# Candunio.net
KiCad netlist of a schematic drawn in Altium Designer
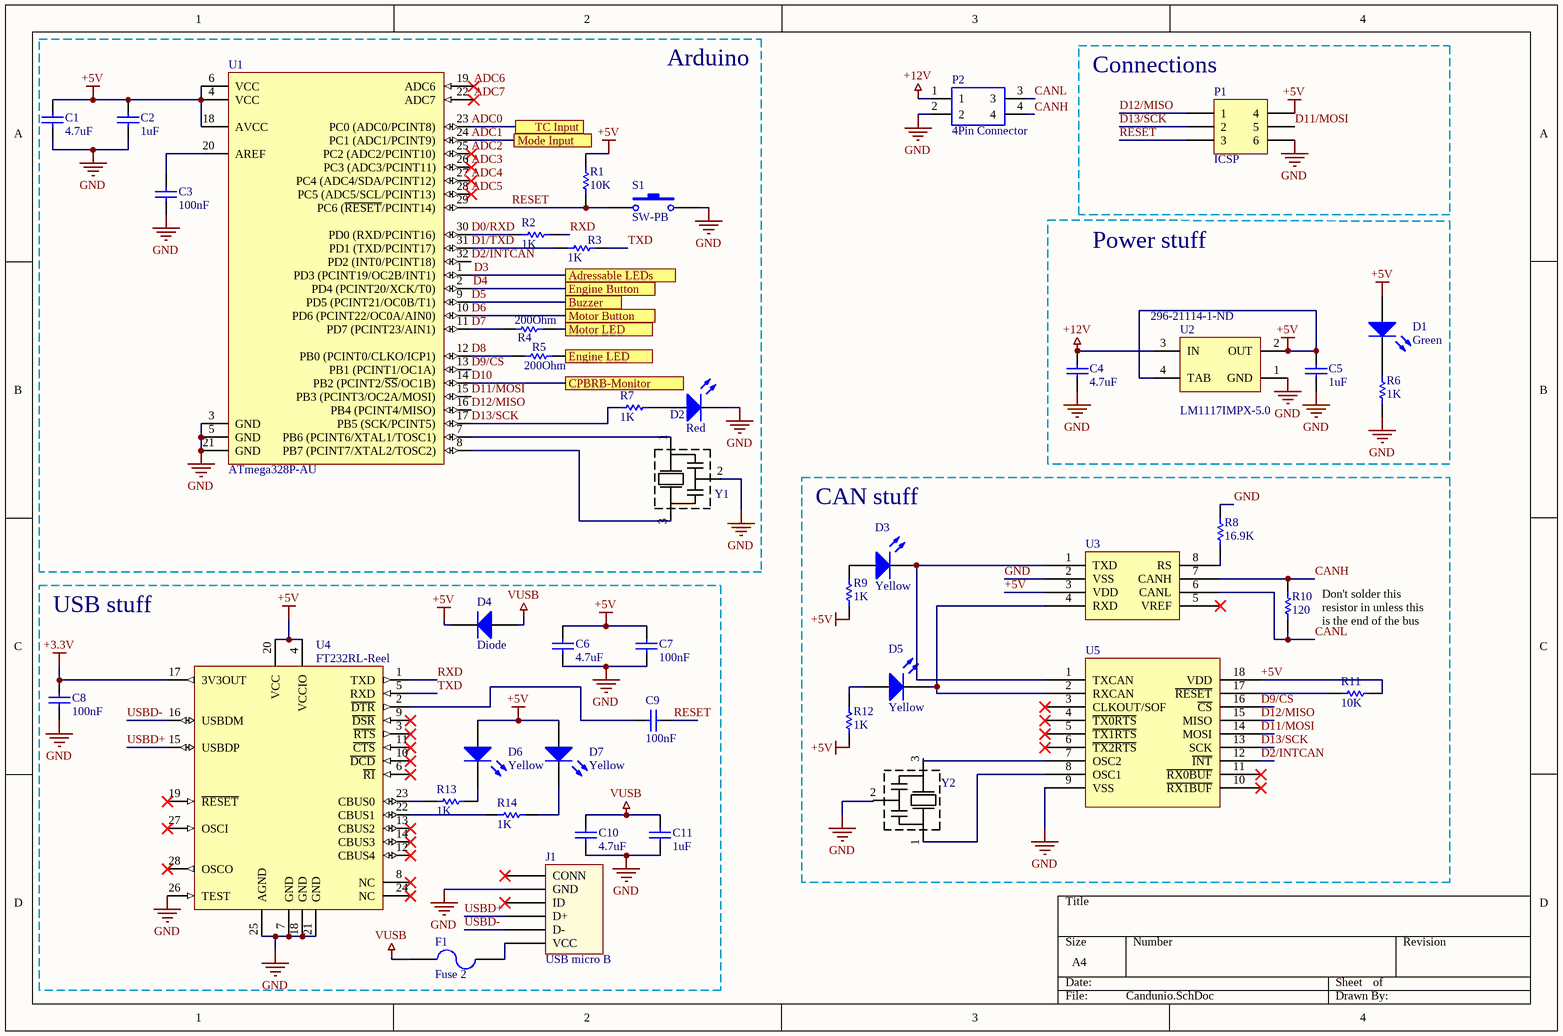
[diagram p0: Candunio.SchDoc]

(export (version "E")
  (design (tool "Eeschema 10.0.6"))
  (components
    (comp (ref "C1")
      (value "4.7uF")
      (footprint "CAPC3216X170N")
      (description "Capacitor (Semiconductor SIM Model)")
      (fields
        (field (name "MANUFACTURER") "Murata")
        (field (name "MANUFACTURER PART NUMBER") "GRM31MR71H105KA88L")
        (field (name "PUBLISHER") "Altium Limited")
      )
      (libsource (lib "Candunio v2018_7_27") (part "Cap Semi"))
    )
    (comp (ref "C2")
      (value "1uF")
      (footprint "CAPC3216X170N")
      (description "Capacitor (Semiconductor SIM Model)")
      (fields
        (field (name "MANUFACTURER") "Murata")
        (field (name "MANUFACTURER PART NUMBER") "GRM31MR71H105KA88L")
        (field (name "PUBLISHER") "Altium Limited")
      )
      (libsource (lib "Candunio v2018_7_27") (part "Cap Semi"))
    )
    (comp (ref "C3")
      (value "100nF")
      (footprint "CAPC3216X170N")
      (description "Capacitor (Semiconductor SIM Model)")
      (fields
        (field (name "MANUFACTURER") "Murata")
        (field (name "MANUFACTURER PART NUMBER") "GRM31MR71H105KA88L")
        (field (name "PUBLISHER") "Altium Limited")
      )
      (libsource (lib "Candunio v2018_7_27") (part "Cap Semi"))
    )
    (comp (ref "C4")
      (value "4.7uF")
      (footprint "CAPC3216X170N")
      (description "Capacitor (Semiconductor SIM Model)")
      (fields
        (field (name "MANUFACTURER") "Murata")
        (field (name "MANUFACTURER PART NUMBER") "GRM31MR71H105KA88L")
        (field (name "PUBLISHER") "Altium Limited")
      )
      (libsource (lib "Candunio v2018_7_27") (part "Cap Semi"))
    )
    (comp (ref "C5")
      (value "1uF")
      (footprint "CAPC3216X170N")
      (description "Capacitor (Semiconductor SIM Model)")
      (fields
        (field (name "MANUFACTURER") "Murata")
        (field (name "MANUFACTURER PART NUMBER") "GRM31MR71H105KA88L")
        (field (name "PUBLISHER") "Altium Limited")
      )
      (libsource (lib "Candunio v2018_7_27") (part "Cap Semi"))
    )
    (comp (ref "C6")
      (value "4.7uF")
      (footprint "CAPC3216X170N")
      (description "Capacitor (Semiconductor SIM Model)")
      (fields
        (field (name "MANUFACTURER") "Murata")
        (field (name "MANUFACTURER PART NUMBER") "GRM31MR71H105KA88L")
        (field (name "PUBLISHER") "Altium Limited")
      )
      (libsource (lib "Candunio v2018_7_27") (part "Cap Semi"))
    )
    (comp (ref "C7")
      (value "100nF")
      (footprint "CAPC3216X170N")
      (description "Capacitor (Semiconductor SIM Model)")
      (fields
        (field (name "MANUFACTURER") "Murata")
        (field (name "MANUFACTURER PART NUMBER") "GRM31MR71H105KA88L")
        (field (name "PUBLISHER") "Altium Limited")
      )
      (libsource (lib "Candunio v2018_7_27") (part "Cap Semi"))
    )
    (comp (ref "C8")
      (value "100nF")
      (footprint "CAPC3216X170N")
      (description "Capacitor (Semiconductor SIM Model)")
      (fields
        (field (name "MANUFACTURER") "Murata")
        (field (name "MANUFACTURER PART NUMBER") "GRM31MR71H105KA88L")
        (field (name "PUBLISHER") "Altium Limited")
      )
      (libsource (lib "Candunio v2018_7_27") (part "Cap Semi"))
    )
    (comp (ref "C9")
      (value "100nF")
      (footprint "CAPC3216X170N")
      (description "Capacitor (Semiconductor SIM Model)")
      (fields
        (field (name "MANUFACTURER") "Murata")
        (field (name "MANUFACTURER PART NUMBER") "GRM31MR71H105KA88L")
        (field (name "PUBLISHER") "Altium Limited")
      )
      (libsource (lib "Candunio v2018_7_27") (part "Cap Semi"))
    )
    (comp (ref "C10")
      (value "4.7uF")
      (footprint "CAPC3216X170N")
      (description "Capacitor (Semiconductor SIM Model)")
      (fields
        (field (name "MANUFACTURER") "Murata")
        (field (name "MANUFACTURER PART NUMBER") "GRM31MR71H105KA88L")
        (field (name "PUBLISHER") "Altium Limited")
      )
      (libsource (lib "Candunio v2018_7_27") (part "Cap Semi"))
    )
    (comp (ref "C11")
      (value "1uF")
      (footprint "CAPC3216X170N")
      (description "Capacitor (Semiconductor SIM Model)")
      (fields
        (field (name "MANUFACTURER") "Murata")
        (field (name "MANUFACTURER PART NUMBER") "GRM31MR71H105KA88L")
        (field (name "PUBLISHER") "Altium Limited")
      )
      (libsource (lib "Candunio v2018_7_27") (part "Cap Semi"))
    )
    (comp (ref "D1")
      (value "Green")
      (footprint "LEDC3216X120NGRN")
      (description "Typical RED, GREEN, YELLOW, AMBER GaAs LED")
      (fields
        (field (name "MANUFACTURER") "Broadcom Avago")
        (field (name "MANUFACTURER PART NUMBER") "HSMG-C150")
        (field (name "PUBLISHER") "Altium Limited")
      )
      (libsource (lib "Miscellaneous Devices") (part "LED2"))
    )
    (comp (ref "D2")
      (value "Red")
      (footprint "LEDC3216X120NRED")
      (description "Typical RED, GREEN, YELLOW, AMBER GaAs LED")
      (fields
        (field (name "MANUFACTURER") "Broadcom Avago")
        (field (name "MANUFACTURER PART NUMBER") "HSMY-C150")
        (field (name "PUBLISHER") "Altium Limited")
      )
      (libsource (lib "Miscellaneous Devices") (part "LED2"))
    )
    (comp (ref "D3")
      (value "Yellow")
      (footprint "LEDC3216X120NYEL")
      (description "Typical RED, GREEN, YELLOW, AMBER GaAs LED")
      (fields
        (field (name "MANUFACTURER") "Broadcom Avago")
        (field (name "MANUFACTURER PART NUMBER") "HSMY-C150")
        (field (name "PUBLISHER") "Altium Limited")
      )
      (libsource (lib "Miscellaneous Devices") (part "LED2"))
    )
    (comp (ref "D4")
      (value "Diode")
      (footprint "DO-220AA")
      (description "Default Diode")
      (fields (field (name "PUBLISHER") "Altium Limited"))
      (libsource (lib "Candunio") (part "Diode"))
    )
    (comp (ref "D5")
      (value "Yellow")
      (footprint "LEDC3216X120NYEL")
      (description "Typical RED, GREEN, YELLOW, AMBER GaAs LED")
      (fields
        (field (name "MANUFACTURER") "Broadcom Avago")
        (field (name "MANUFACTURER PART NUMBER") "HSMY-C150")
        (field (name "PUBLISHER") "Altium Limited")
      )
      (libsource (lib "Miscellaneous Devices") (part "LED2"))
    )
    (comp (ref "D6")
      (value "Yellow")
      (footprint "LEDC3216X120NYEL")
      (description "Typical RED, GREEN, YELLOW, AMBER GaAs LED")
      (fields
        (field (name "MANUFACTURER") "Broadcom Avago")
        (field (name "MANUFACTURER PART NUMBER") "HSMY-C150")
        (field (name "PUBLISHER") "Altium Limited")
      )
      (libsource (lib "Miscellaneous Devices") (part "LED2"))
    )
    (comp (ref "D7")
      (value "Yellow")
      (footprint "LEDC3216X120NYEL")
      (description "Typical RED, GREEN, YELLOW, AMBER GaAs LED")
      (fields
        (field (name "MANUFACTURER") "Broadcom Avago")
        (field (name "MANUFACTURER PART NUMBER") "HSMY-C150")
        (field (name "PUBLISHER") "Altium Limited")
      )
      (libsource (lib "Miscellaneous Devices") (part "LED2"))
    )
    (comp (ref "F1")
      (value "Fuse 2")
      (footprint "FUSC4632X85N")
      (description "Fuse")
      (fields
        (field (name "PART NUMBER") "MF-MSMF050-2")
        (field (name "MANUFACTURER") "Bourns")
        (field (name "PUBLISHER") "Altium Limited")
      )
      (libsource (lib "PowerDistLib") (part "Fuse 2"))
    )
    (comp (ref "J1")
      (value "USB micro B")
      (footprint "1050170001")
      (description "CONN SM TH USB MICRO MODIFIED FOR DRILL")
      (fields (field (name "PART NUMBER") "WM1399CT-ND"))
      (libsource (lib "electronpowered") (part "1050170001"))
    )
    (comp (ref "P1")
      (value "ICSP")
      (footprint "Pin Header 2x3 TH Pitch 2.54mm")
      (description "Header, 3-Pin, Dual row")
      (fields (field (name "PUBLISHER") "Altium Limited"))
      (libsource (lib "Miscellaneous Connectors") (part "Header 3X2A"))
    )
    (comp (ref "P2")
      (value "4Pin Connector")
      (footprint "4Pin connector Molex")
      (description "Connector Header Through Hole 4 position 0.118\" (3.00mm) \r\n0430450413")
      (fields (field (name "MANUFACTURER_PART_NUMBER") "0430450413"))
      (libsource (lib "Connectors") (part "4Pin Connector"))
    )
    (comp (ref "R1")
      (value "10K")
      (footprint "RESC3216X60N")
      (description "Resistor")
      (fields
        (field (name "MANUFACTURER") "Stackpole Electronics")
        (field (name "MANUFACTURER PART NUMBER") "RNCP1206FTD1K00")
      )
      (libsource (lib "Miscellaneous Devices") (part "Res1"))
    )
    (comp (ref "R2")
      (value "1K")
      (footprint "RESC3216X60N")
      (description "Resistor")
      (fields
        (field (name "MANUFACTURER") "Stackpole Electronics")
        (field (name "MANUFACTURER PART NUMBER") "RNCP1206FTD1K00")
      )
      (libsource (lib "Miscellaneous Devices") (part "Res1"))
    )
    (comp (ref "R3")
      (value "1K")
      (footprint "RESC3216X60N")
      (description "Resistor")
      (fields
        (field (name "MANUFACTURER") "Stackpole Electronics")
        (field (name "MANUFACTURER PART NUMBER") "RNCP1206FTD1K00")
      )
      (libsource (lib "Miscellaneous Devices") (part "Res1"))
    )
    (comp (ref "R4")
      (value "200Ohm")
      (footprint "RESC3216X60N")
      (description "Resistor")
      (fields
        (field (name "MANUFACTURER") "Stackpole Electronics")
        (field (name "MANUFACTURER PART NUMBER") "RNCP1206FTD200R")
      )
      (libsource (lib "Miscellaneous Devices") (part "Res1"))
    )
    (comp (ref "R5")
      (value "200Ohm")
      (footprint "RESC3216X60N")
      (description "Resistor")
      (fields
        (field (name "MANUFACTURER") "Stackpole Electronics")
        (field (name "MANUFACTURER PART NUMBER") "RNCP1206FTD200R")
      )
      (libsource (lib "Miscellaneous Devices") (part "Res1"))
    )
    (comp (ref "R6")
      (value "1K")
      (footprint "RESC3216X60N")
      (description "Resistor")
      (fields
        (field (name "MANUFACTURER") "Stackpole Electronics")
        (field (name "MANUFACTURER PART NUMBER") "RNCP1206FTD1K00")
      )
      (libsource (lib "Miscellaneous Devices") (part "Res1"))
    )
    (comp (ref "R7")
      (value "1K")
      (footprint "RESC3216X60N")
      (description "Resistor")
      (fields
        (field (name "MANUFACTURER") "Stackpole Electronics")
        (field (name "MANUFACTURER PART NUMBER") "RNCP1206FTD1K00")
      )
      (libsource (lib "Miscellaneous Devices") (part "Res1"))
    )
    (comp (ref "R8")
      (value "16.9K")
      (footprint "RESC3216X60N")
      (description "Resistor")
      (fields
        (field (name "MANUFACTURER") "TE Connectivity Holsworthy")
        (field (name "MANUFACTURER PART NUMBER") "CRGH1206F16K9")
      )
      (libsource (lib "Miscellaneous Devices") (part "Res1"))
    )
    (comp (ref "R9")
      (value "1K")
      (footprint "RESC3216X60N")
      (description "Resistor")
      (fields
        (field (name "MANUFACTURER") "Stackpole Electronics")
        (field (name "MANUFACTURER PART NUMBER") "RNCP1206FTD1K00")
      )
      (libsource (lib "Miscellaneous Devices") (part "Res1"))
    )
    (comp (ref "R10")
      (value "120")
      (footprint "RESC3216X60N")
      (description "Resistor")
      (fields
        (field (name "MANUFACTURER") "Vishay")
        (field (name "MANUFACTURER PART NUMBER") "CRCW1206120RFKEAHP")
      )
      (libsource (lib "Miscellaneous Devices") (part "Res1"))
    )
    (comp (ref "R11")
      (value "10K")
      (footprint "RESC3216X60N")
      (description "Resistor")
      (fields
        (field (name "MANUFACTURER") "Stackpole Electronics")
        (field (name "MANUFACTURER PART NUMBER") "RNCP1206FTD10K0")
      )
      (libsource (lib "Miscellaneous Devices") (part "Res1"))
    )
    (comp (ref "R12")
      (value "1K")
      (footprint "RESC3216X60N")
      (description "Resistor")
      (fields
        (field (name "MANUFACTURER") "Stackpole Electronics")
        (field (name "MANUFACTURER PART NUMBER") "RNCP1206FTD1K00")
      )
      (libsource (lib "Miscellaneous Devices") (part "Res1"))
    )
    (comp (ref "R13")
      (value "1K")
      (footprint "RESC3216X60N")
      (description "Resistor")
      (fields
        (field (name "MANUFACTURER") "Stackpole Electronics")
        (field (name "MANUFACTURER PART NUMBER") "RNCP1206FTD1K00")
      )
      (libsource (lib "Miscellaneous Devices") (part "Res1"))
    )
    (comp (ref "R14")
      (value "1K")
      (footprint "RESC3216X60N")
      (description "Resistor")
      (fields
        (field (name "MANUFACTURER") "Stackpole Electronics")
        (field (name "MANUFACTURER PART NUMBER") "RNCP1206FTD1K00")
      )
      (libsource (lib "Miscellaneous Devices") (part "Res1"))
    )
    (comp (ref "S1")
      (value "SW-PB")
      (footprint "SMDswitch_1206")
      (description "Switch")
      (fields
        (field (name "MANUFACTURER") "ITT C&K")
        (field (name "MANUFACTURER PART NUMBER") "KXT331LHS")
        (field (name "PUBLISHER") "Altium Limited")
      )
      (libsource (lib "Miscellaneous Devices") (part "SW-PB"))
    )
    (comp (ref "U1")
      (value "ATmega328P-AU")
      (footprint "QFP80P900X900X120-32N")
      (fields (field (name "PUBLISHER") "Altium Limited"))
      (libsource (lib "Atmel Microcontroller 8-Bit megaAVR") (part "ATmega328P-AU"))
    )
    (comp (ref "U2")
      (value "LM1117IMPX-5.0")
      (footprint "SOT230P700X180-4N")
      (description "800mA Low-Dropout Linear Regulator, 4-pin SOT-223")
      (fields
        (field (name "PARTNUMBER") "LM1117IMPX-5.0/NOPBCT-ND")
        (field (name "MANUFACTURER") "National Semiconductor")
        (field (name "SUPPLIER PART NUMBER") "296-21114-1-ND")
        (field (name "PUBLISHER") "Altium Limited")
      )
      (libsource (lib "NSC LDO") (part "LM1117IMPX-5.0"))
    )
    (comp (ref "U3")
      (value "MCP2551-E/SN")
      (footprint "SOIC127P600X175-8N")
      (description "SOIC")
      (libsource (lib "AMSComponents") (part "MCP2551-E/SN"))
    )
    (comp (ref "U4")
      (value "FT232RL-Reel")
      (footprint "SOP65P780X200-28N")
      (description "USB UART Asynchronous Serial Data Transfer Chip, SSOP-28, Tape and Reel")
      (fields
        (field (name "MANUFACTURER") "FTDI")
        (field (name "MANUFACTURER PART NUMBER") "FT232RL-REEL")
        (field (name "PUBLISHER") "Altium Limited")
      )
      (libsource (lib "FTDI Communication UART") (part "FT232RL-Reel"))
    )
    (comp (ref "U5")
      (value "MCP2515-E/ST")
      (footprint "SOIC127P1030X265-18N")
      (description "SOIC")
      (libsource (lib "AMSComponents") (part "MCP2515-E/ST"))
    )
    (comp (ref "Y1")
      (value "CSTCE16M0V53-R0")
      (footprint "CSTCE_G")
      (fields
        (field (name "MANUFACTURER") "Murata")
        (field (name "MANUFACTURER PART NUMBER") "CSTCE16M0V53C-R0")
        (field (name "TOLERANCE") "0.5%")
      )
      (libsource (lib "AMSComponents") (part "CSTCE16M0V53-R0"))
    )
    (comp (ref "Y2")
      (value "CSTCE16M0V53-R0")
      (footprint "CSTCE_G")
      (fields
        (field (name "MANUFACTURER") "Murata")
        (field (name "MANUFACTURER PART NUMBER") "CSTCE16M0V53C-R0")
        (field (name "TOLERANCE") "0.5%")
      )
      (libsource (lib "AMSComponents") (part "CSTCE16M0V53-R0"))
    )
  )
  (nets
    (net (code "1") (name "+3.3V") (class "Default")
      (node (ref "C8") (pin "2") (pinfunction "2_2") (pintype "passive"))
      (node (ref "U4") (pin "17") (pinfunction "3V3OUT_17") (pintype "output"))
    )
    (net (code "2") (name "+5V") (class "Default")
      (node (ref "C1") (pin "1") (pinfunction "1_1") (pintype "passive"))
      (node (ref "C2") (pin "2") (pinfunction "2_2") (pintype "passive"))
      (node (ref "C5") (pin "2") (pinfunction "2_2") (pintype "passive"))
      (node (ref "C6") (pin "2") (pinfunction "2_2") (pintype "passive"))
      (node (ref "C7") (pin "2") (pinfunction "2_2") (pintype "passive"))
      (node (ref "D1") (pin "1") (pinfunction "A_1") (pintype "passive"))
      (node (ref "D4") (pin "2") (pinfunction "K_2") (pintype "passive"))
      (node (ref "D6") (pin "1") (pinfunction "A_1") (pintype "passive"))
      (node (ref "D7") (pin "1") (pinfunction "A_1") (pintype "passive"))
      (node (ref "P1") (pin "4") (pinfunction "4_4") (pintype "passive"))
      (node (ref "R1") (pin "1") (pinfunction "1_1") (pintype "passive"))
      (node (ref "R11") (pin "2") (pinfunction "2_2") (pintype "passive"))
      (node (ref "R12") (pin "2") (pinfunction "2_2") (pintype "passive"))
      (node (ref "R9") (pin "1") (pinfunction "1_1") (pintype "passive"))
      (node (ref "U1") (pin "18") (pinfunction "AVCC_18") (pintype "power_in"))
      (node (ref "U1") (pin "4") (pinfunction "VCC_4") (pintype "power_in"))
      (node (ref "U1") (pin "6") (pinfunction "VCC_6") (pintype "power_in"))
      (node (ref "U2") (pin "2") (pinfunction "OUT_2") (pintype "power_in"))
      (node (ref "U2") (pin "4") (pinfunction "TAB_4") (pintype "power_in"))
      (node (ref "U3") (pin "3") (pinfunction "VDD_3") (pintype "passive"))
      (node (ref "U4") (pin "20") (pinfunction "VCC_20") (pintype "power_in"))
      (node (ref "U4") (pin "4") (pinfunction "VCCIO_4") (pintype "power_in"))
      (node (ref "U5") (pin "18") (pinfunction "VDD_18") (pintype "passive"))
    )
    (net (code "3") (name "+12V") (class "Default")
      (node (ref "C4") (pin "2") (pinfunction "2_2") (pintype "passive"))
      (node (ref "P2") (pin "1") (pinfunction "1_1") (pintype "passive"))
      (node (ref "U2") (pin "3") (pinfunction "IN_3") (pintype "power_in"))
    )
    (net (code "4") (name "/ADC0") (class "Default")
      (node (ref "U1") (pin "23") (pinfunction "PC0_(ADC0/PCINT8)_23") (pintype "bidirectional"))
    )
    (net (code "5") (name "/ADC1") (class "Default")
      (node (ref "U1") (pin "24") (pinfunction "PC1_(ADC1/PCINT9)_24") (pintype "bidirectional"))
    )
    (net (code "6") (name "/ADC2") (class "Default")
      (node (ref "U1") (pin "25") (pinfunction "PC2_(ADC2/PCINT10)_25") (pintype "bidirectional+no_connect"))
    )
    (net (code "7") (name "/ADC3") (class "Default")
      (node (ref "U1") (pin "26") (pinfunction "PC3_(ADC3/PCINT11)_26") (pintype "bidirectional+no_connect"))
    )
    (net (code "8") (name "/ADC4") (class "Default")
      (node (ref "U1") (pin "27") (pinfunction "PC4_(ADC4/SDA/PCINT12)_27") (pintype "bidirectional+no_connect"))
    )
    (net (code "9") (name "/ADC5") (class "Default")
      (node (ref "U1") (pin "28") (pinfunction "PC5_(ADC5/SCL/PCINT13)_28") (pintype "bidirectional+no_connect"))
    )
    (net (code "10") (name "/ADC6") (class "Default")
      (node (ref "U1") (pin "19") (pinfunction "ADC6_19") (pintype "input+no_connect"))
    )
    (net (code "11") (name "/ADC7") (class "Default")
      (node (ref "U1") (pin "22") (pinfunction "ADC7_22") (pintype "input+no_connect"))
    )
    (net (code "12") (name "/CANH") (class "Default")
      (node (ref "P2") (pin "4") (pinfunction "4_4") (pintype "passive"))
      (node (ref "R10") (pin "1") (pinfunction "1_1") (pintype "passive"))
      (node (ref "U3") (pin "7") (pinfunction "CANH_7") (pintype "passive"))
    )
    (net (code "13") (name "/CANL") (class "Default")
      (node (ref "P2") (pin "3") (pinfunction "3_3") (pintype "passive"))
      (node (ref "R10") (pin "2") (pinfunction "2_2") (pintype "passive"))
      (node (ref "U3") (pin "6") (pinfunction "CANL_6") (pintype "passive"))
    )
    (net (code "14") (name "/D0{slash}RXD") (class "Default")
      (node (ref "R2") (pin "1") (pinfunction "1_1") (pintype "passive"))
      (node (ref "U1") (pin "30") (pinfunction "PD0_(RXD/PCINT16)_30") (pintype "bidirectional"))
    )
    (net (code "15") (name "/D1{slash}TXD") (class "Default")
      (node (ref "R3") (pin "1") (pinfunction "1_1") (pintype "passive"))
      (node (ref "U1") (pin "31") (pinfunction "PD1_(TXD/PCINT17)_31") (pintype "bidirectional"))
    )
    (net (code "16") (name "/D2{slash}INTCAN") (class "Default")
      (node (ref "U1") (pin "32") (pinfunction "PD2_(INT0/PCINT18)_32") (pintype "bidirectional"))
      (node (ref "U5") (pin "12") (pinfunction "~{INT}_12") (pintype "passive"))
    )
    (net (code "17") (name "/D3") (class "Default")
      (node (ref "U1") (pin "1") (pinfunction "PD3_(PCINT19/OC2B/INT1)_1") (pintype "bidirectional"))
    )
    (net (code "18") (name "/D4") (class "Default")
      (node (ref "U1") (pin "2") (pinfunction "PD4_(PCINT20/XCK/T0)_2") (pintype "bidirectional"))
    )
    (net (code "19") (name "/D5") (class "Default")
      (node (ref "U1") (pin "9") (pinfunction "PD5_(PCINT21/OC0B/T1)_9") (pintype "bidirectional"))
    )
    (net (code "20") (name "/D6") (class "Default")
      (node (ref "U1") (pin "10") (pinfunction "PD6_(PCINT22/OC0A/AIN0)_10") (pintype "bidirectional"))
    )
    (net (code "21") (name "/D7") (class "Default")
      (node (ref "R4") (pin "1") (pinfunction "1_1") (pintype "passive"))
      (node (ref "U1") (pin "11") (pinfunction "PD7_(PCINT23/AIN1)_11") (pintype "bidirectional"))
    )
    (net (code "22") (name "/D8") (class "Default")
      (node (ref "R5") (pin "1") (pinfunction "1_1") (pintype "passive"))
      (node (ref "U1") (pin "12") (pinfunction "PB0_(PCINT0/CLKO/ICP1)_12") (pintype "bidirectional"))
    )
    (net (code "23") (name "/D9{slash}CS") (class "Default")
      (node (ref "U1") (pin "13") (pinfunction "PB1_(PCINT1/OC1A)_13") (pintype "bidirectional"))
      (node (ref "U5") (pin "16") (pinfunction "~{CS}_16") (pintype "passive"))
    )
    (net (code "24") (name "/D10") (class "Default")
      (node (ref "U1") (pin "14") (pinfunction "PB2_(PCINT2/~{SS}/OC1B)_14") (pintype "bidirectional"))
    )
    (net (code "25") (name "/D11{slash}MOSI") (class "Default")
      (node (ref "P1") (pin "5") (pinfunction "5_5") (pintype "passive"))
      (node (ref "U1") (pin "15") (pinfunction "PB3_(PCINT3/OC2A/MOSI)_15") (pintype "bidirectional"))
      (node (ref "U5") (pin "14") (pinfunction "MOSI_14") (pintype "passive"))
    )
    (net (code "26") (name "/D12{slash}MISO") (class "Default")
      (node (ref "P1") (pin "1") (pinfunction "1_1") (pintype "passive"))
      (node (ref "U1") (pin "16") (pinfunction "PB4_(PCINT4/MISO)_16") (pintype "bidirectional"))
      (node (ref "U5") (pin "15") (pinfunction "MISO_15") (pintype "passive"))
    )
    (net (code "27") (name "/D13{slash}SCK") (class "Default")
      (node (ref "P1") (pin "2") (pinfunction "2_2") (pintype "passive"))
      (node (ref "R7") (pin "2") (pinfunction "2_2") (pintype "passive"))
      (node (ref "U1") (pin "17") (pinfunction "PB5_(SCK/PCINT5)_17") (pintype "bidirectional"))
      (node (ref "U5") (pin "13") (pinfunction "SCK_13") (pintype "passive"))
    )
    (net (code "28") (name "/Engine LED") (class "Default")
      (node (ref "R5") (pin "2") (pinfunction "2_2") (pintype "passive"))
    )
    (net (code "29") (name "/Motor LED") (class "Default")
      (node (ref "R4") (pin "2") (pinfunction "2_2") (pintype "passive"))
    )
    (net (code "30") (name "/RESET") (class "Default")
      (node (ref "C9") (pin "2") (pinfunction "2_2") (pintype "passive"))
      (node (ref "P1") (pin "3") (pinfunction "3_3") (pintype "passive"))
      (node (ref "R1") (pin "2") (pinfunction "2_2") (pintype "passive"))
      (node (ref "S1") (pin "1") (pinfunction "1_1") (pintype "passive"))
      (node (ref "U1") (pin "29") (pinfunction "PC6_(~{RESET}/PCINT14)_29") (pintype "bidirectional"))
    )
    (net (code "31") (name "/RXD") (class "Default")
      (node (ref "R2") (pin "2") (pinfunction "2_2") (pintype "passive"))
      (node (ref "U4") (pin "1") (pinfunction "TXD_1") (pintype "output"))
    )
    (net (code "32") (name "/TXD") (class "Default")
      (node (ref "R3") (pin "2") (pinfunction "2_2") (pintype "passive"))
      (node (ref "U4") (pin "5") (pinfunction "RXD_5") (pintype "input"))
    )
    (net (code "33") (name "/USBD+") (class "Default")
      (node (ref "J1") (pin "3") (pinfunction "D+_3") (pintype "passive"))
      (node (ref "U4") (pin "15") (pinfunction "USBDP_15") (pintype "bidirectional"))
    )
    (net (code "34") (name "/USBD-") (class "Default")
      (node (ref "J1") (pin "2") (pinfunction "D-_2") (pintype "passive"))
      (node (ref "U4") (pin "16") (pinfunction "USBDM_16") (pintype "bidirectional"))
    )
    (net (code "35") (name "GND") (class "Default")
      (node (ref "C1") (pin "2") (pinfunction "2_2") (pintype "passive"))
      (node (ref "C10") (pin "1") (pinfunction "1_1") (pintype "passive"))
      (node (ref "C11") (pin "1") (pinfunction "1_1") (pintype "passive"))
      (node (ref "C2") (pin "1") (pinfunction "1_1") (pintype "passive"))
      (node (ref "C3") (pin "1") (pinfunction "1_1") (pintype "passive"))
      (node (ref "C4") (pin "1") (pinfunction "1_1") (pintype "passive"))
      (node (ref "C5") (pin "1") (pinfunction "1_1") (pintype "passive"))
      (node (ref "C6") (pin "1") (pinfunction "1_1") (pintype "passive"))
      (node (ref "C7") (pin "1") (pinfunction "1_1") (pintype "passive"))
      (node (ref "C8") (pin "1") (pinfunction "1_1") (pintype "passive"))
      (node (ref "D2") (pin "2") (pinfunction "K_2") (pintype "passive"))
      (node (ref "J1") (pin "5") (pinfunction "GND_5") (pintype "passive"))
      (node (ref "P1") (pin "6") (pinfunction "6_6") (pintype "passive"))
      (node (ref "P2") (pin "2") (pinfunction "2_2") (pintype "passive"))
      (node (ref "R6") (pin "2") (pinfunction "2_2") (pintype "passive"))
      (node (ref "R8") (pin "1") (pinfunction "1_1") (pintype "passive"))
      (node (ref "S1") (pin "2") (pinfunction "2_2") (pintype "passive"))
      (node (ref "U1") (pin "21") (pinfunction "GND_21") (pintype "power_in"))
      (node (ref "U1") (pin "3") (pinfunction "GND_3") (pintype "power_in"))
      (node (ref "U1") (pin "5") (pinfunction "GND_5") (pintype "power_in"))
      (node (ref "U2") (pin "1") (pinfunction "GND_1") (pintype "power_in"))
      (node (ref "U3") (pin "2") (pinfunction "VSS_2") (pintype "passive"))
      (node (ref "U4") (pin "18") (pinfunction "GND_18") (pintype "power_in"))
      (node (ref "U4") (pin "21") (pinfunction "GND_21") (pintype "power_in"))
      (node (ref "U4") (pin "25") (pinfunction "AGND_25") (pintype "power_in"))
      (node (ref "U4") (pin "26") (pinfunction "TEST_26") (pintype "input"))
      (node (ref "U4") (pin "7") (pinfunction "GND_7") (pintype "power_in"))
      (node (ref "U5") (pin "9") (pinfunction "VSS_9") (pintype "passive"))
      (node (ref "Y1") (pin "2") (pinfunction "2_2") (pintype "passive"))
      (node (ref "Y2") (pin "2") (pinfunction "2_2") (pintype "passive"))
    )
    (net (code "36") (name "Net-(D1-K)") (class "Default")
      (node (ref "D1") (pin "2") (pinfunction "K_2") (pintype "passive"))
      (node (ref "R6") (pin "1") (pinfunction "1_1") (pintype "passive"))
    )
    (net (code "37") (name "Net-(D3-A)") (class "Default")
      (node (ref "D3") (pin "1") (pinfunction "A_1") (pintype "passive"))
      (node (ref "R9") (pin "2") (pinfunction "2_2") (pintype "passive"))
    )
    (net (code "38") (name "Net-(D3-K)") (class "Default")
      (node (ref "D3") (pin "2") (pinfunction "K_2") (pintype "passive"))
      (node (ref "U3") (pin "1") (pinfunction "TXD_1") (pintype "passive"))
      (node (ref "U5") (pin "1") (pinfunction "TXCAN_1") (pintype "passive"))
    )
    (net (code "39") (name "Net-(D5-A)") (class "Default")
      (node (ref "D5") (pin "1") (pinfunction "A_1") (pintype "passive"))
      (node (ref "R12") (pin "1") (pinfunction "1_1") (pintype "passive"))
    )
    (net (code "40") (name "Net-(D5-K)") (class "Default")
      (node (ref "D5") (pin "2") (pinfunction "K_2") (pintype "passive"))
      (node (ref "U3") (pin "4") (pinfunction "RXD_4") (pintype "passive"))
      (node (ref "U5") (pin "2") (pinfunction "RXCAN_2") (pintype "passive"))
    )
    (net (code "41") (name "Net-(D6-K)") (class "Default")
      (node (ref "D6") (pin "2") (pinfunction "K_2") (pintype "passive"))
      (node (ref "R13") (pin "2") (pinfunction "2_2") (pintype "passive"))
    )
    (net (code "42") (name "Net-(D7-K)") (class "Default")
      (node (ref "D7") (pin "2") (pinfunction "K_2") (pintype "passive"))
      (node (ref "R14") (pin "2") (pinfunction "2_2") (pintype "passive"))
    )
    (net (code "43") (name "Net-(J1-VCC)") (class "Default")
      (node (ref "F1") (pin "2") (pinfunction "2_2") (pintype "passive"))
      (node (ref "J1") (pin "1") (pinfunction "VCC_1") (pintype "passive"))
    )
    (net (code "44") (name "Net-(U1-AREF)") (class "Default")
      (node (ref "C3") (pin "2") (pinfunction "2_2") (pintype "passive"))
      (node (ref "U1") (pin "20") (pinfunction "AREF_20") (pintype "passive"))
    )
    (net (code "45") (name "Net-(U1-PB6_(PCINT6{slash}XTAL1{slash}TOSC1))") (class "Default")
      (node (ref "U1") (pin "7") (pinfunction "PB6_(PCINT6/XTAL1/TOSC1)_7") (pintype "bidirectional"))
      (node (ref "Y1") (pin "1") (pinfunction "1_1") (pintype "passive"))
    )
    (net (code "46") (name "Net-(U1-PB7_(PCINT7{slash}XTAL2{slash}TOSC2))") (class "Default")
      (node (ref "U1") (pin "8") (pinfunction "PB7_(PCINT7/XTAL2/TOSC2)_8") (pintype "bidirectional"))
      (node (ref "Y1") (pin "3") (pinfunction "3_3") (pintype "passive"))
    )
    (net (code "47") (name "Net-(U3-RS)") (class "Default")
      (node (ref "R8") (pin "2") (pinfunction "2_2") (pintype "passive"))
      (node (ref "U3") (pin "8") (pinfunction "RS_8") (pintype "passive"))
    )
    (net (code "48") (name "Net-(U4-CBUS0)") (class "Default")
      (node (ref "R13") (pin "1") (pinfunction "1_1") (pintype "passive"))
      (node (ref "U4") (pin "23") (pinfunction "CBUS0_23") (pintype "bidirectional"))
    )
    (net (code "49") (name "Net-(U4-CBUS1)") (class "Default")
      (node (ref "R14") (pin "1") (pinfunction "1_1") (pintype "passive"))
      (node (ref "U4") (pin "22") (pinfunction "CBUS1_22") (pintype "bidirectional"))
    )
    (net (code "50") (name "Net-(U4-~{DTR})") (class "Default")
      (node (ref "C9") (pin "1") (pinfunction "1_1") (pintype "passive"))
      (node (ref "U4") (pin "2") (pinfunction "~{DTR}_2") (pintype "output"))
    )
    (net (code "51") (name "Net-(U5-OSC1)") (class "Default")
      (node (ref "U5") (pin "8") (pinfunction "OSC1_8") (pintype "passive"))
      (node (ref "Y2") (pin "1") (pinfunction "1_1") (pintype "passive"))
    )
    (net (code "52") (name "Net-(U5-OSC2)") (class "Default")
      (node (ref "U5") (pin "7") (pinfunction "OSC2_7") (pintype "passive"))
      (node (ref "Y2") (pin "3") (pinfunction "3_3") (pintype "passive"))
    )
    (net (code "53") (name "Net-(U5-~{RESET})") (class "Default")
      (node (ref "R11") (pin "1") (pinfunction "1_1") (pintype "passive"))
      (node (ref "U5") (pin "17") (pinfunction "~{RESET}_17") (pintype "passive"))
    )
    (net (code "54") (name "VUSB") (class "Default")
      (node (ref "C10") (pin "2") (pinfunction "2_2") (pintype "passive"))
      (node (ref "C11") (pin "2") (pinfunction "2_2") (pintype "passive"))
      (node (ref "D4") (pin "1") (pinfunction "A_1") (pintype "passive"))
      (node (ref "F1") (pin "1") (pinfunction "1_1") (pintype "passive"))
    )
    (net (code "55") (name "unconnected-(D2-A-Pad1)") (class "Default")
      (node (ref "D2") (pin "1") (pinfunction "A_1") (pintype "passive"))
    )
    (net (code "56") (name "unconnected-(J1-CONN-Pad0)") (class "Default")
      (node (ref "J1") (pin "0") (pinfunction "CONN_0") (pintype "passive+no_connect"))
    )
    (net (code "57") (name "unconnected-(J1-ID-Pad4)") (class "Default")
      (node (ref "J1") (pin "4") (pinfunction "ID_4") (pintype "passive+no_connect"))
    )
    (net (code "58") (name "unconnected-(R7-Pad1)") (class "Default")
      (node (ref "R7") (pin "1") (pinfunction "1_1") (pintype "passive"))
    )
    (net (code "59") (name "unconnected-(U3-VREF-Pad5)") (class "Default")
      (node (ref "U3") (pin "5") (pinfunction "VREF_5") (pintype "passive+no_connect"))
    )
    (net (code "60") (name "unconnected-(U4-CBUS2-Pad13)") (class "Default")
      (node (ref "U4") (pin "13") (pinfunction "CBUS2_13") (pintype "bidirectional+no_connect"))
    )
    (net (code "61") (name "unconnected-(U4-CBUS3-Pad14)") (class "Default")
      (node (ref "U4") (pin "14") (pinfunction "CBUS3_14") (pintype "bidirectional+no_connect"))
    )
    (net (code "62") (name "unconnected-(U4-CBUS4-Pad12)") (class "Default")
      (node (ref "U4") (pin "12") (pinfunction "CBUS4_12") (pintype "bidirectional+no_connect"))
    )
    (net (code "63") (name "unconnected-(U4-NC-Pad8)") (class "Default")
      (node (ref "U4") (pin "8") (pinfunction "NC_8") (pintype "passive+no_connect"))
    )
    (net (code "64") (name "unconnected-(U4-NC-Pad24)") (class "Default")
      (node (ref "U4") (pin "24") (pinfunction "NC_24") (pintype "passive+no_connect"))
    )
    (net (code "65") (name "unconnected-(U4-OSCI-Pad27)") (class "Default")
      (node (ref "U4") (pin "27") (pinfunction "OSCI_27") (pintype "input+no_connect"))
    )
    (net (code "66") (name "unconnected-(U4-OSCO-Pad28)") (class "Default")
      (node (ref "U4") (pin "28") (pinfunction "OSCO_28") (pintype "output+no_connect"))
    )
    (net (code "67") (name "unconnected-(U4-~{CTS}-Pad11)") (class "Default")
      (node (ref "U4") (pin "11") (pinfunction "~{CTS}_11") (pintype "input+no_connect"))
    )
    (net (code "68") (name "unconnected-(U4-~{DCD}-Pad10)") (class "Default")
      (node (ref "U4") (pin "10") (pinfunction "~{DCD}_10") (pintype "input+no_connect"))
    )
    (net (code "69") (name "unconnected-(U4-~{DSR}-Pad9)") (class "Default")
      (node (ref "U4") (pin "9") (pinfunction "~{DSR}_9") (pintype "input+no_connect"))
    )
    (net (code "70") (name "unconnected-(U4-~{RESET}-Pad19)") (class "Default")
      (node (ref "U4") (pin "19") (pinfunction "~{RESET}_19") (pintype "input+no_connect"))
    )
    (net (code "71") (name "unconnected-(U4-~{RI}-Pad6)") (class "Default")
      (node (ref "U4") (pin "6") (pinfunction "~{RI}_6") (pintype "input+no_connect"))
    )
    (net (code "72") (name "unconnected-(U4-~{RTS}-Pad3)") (class "Default")
      (node (ref "U4") (pin "3") (pinfunction "~{RTS}_3") (pintype "output+no_connect"))
    )
    (net (code "73") (name "unconnected-(U5-CLKOUT{slash}SOF-Pad3)") (class "Default")
      (node (ref "U5") (pin "3") (pinfunction "CLKOUT/SOF_3") (pintype "passive+no_connect"))
    )
    (net (code "74") (name "unconnected-(U5-~{RX0BUF}-Pad11)") (class "Default")
      (node (ref "U5") (pin "11") (pinfunction "~{RX0BUF}_11") (pintype "passive+no_connect"))
    )
    (net (code "75") (name "unconnected-(U5-~{RX1BUF}-Pad10)") (class "Default")
      (node (ref "U5") (pin "10") (pinfunction "~{RX1BUF}_10") (pintype "passive+no_connect"))
    )
    (net (code "76") (name "unconnected-(U5-~{TX0RTS}-Pad4)") (class "Default")
      (node (ref "U5") (pin "4") (pinfunction "~{TX0RTS}_4") (pintype "passive+no_connect"))
    )
    (net (code "77") (name "unconnected-(U5-~{TX1RTS}-Pad5)") (class "Default")
      (node (ref "U5") (pin "5") (pinfunction "~{TX1RTS}_5") (pintype "passive+no_connect"))
    )
    (net (code "78") (name "unconnected-(U5-~{TX2RTS}-Pad6)") (class "Default")
      (node (ref "U5") (pin "6") (pinfunction "~{TX2RTS}_6") (pintype "passive+no_connect"))
    )
  )
)
